# through_hole_mk1.net
KiCad netlist of a schematic drawn in EAGLE
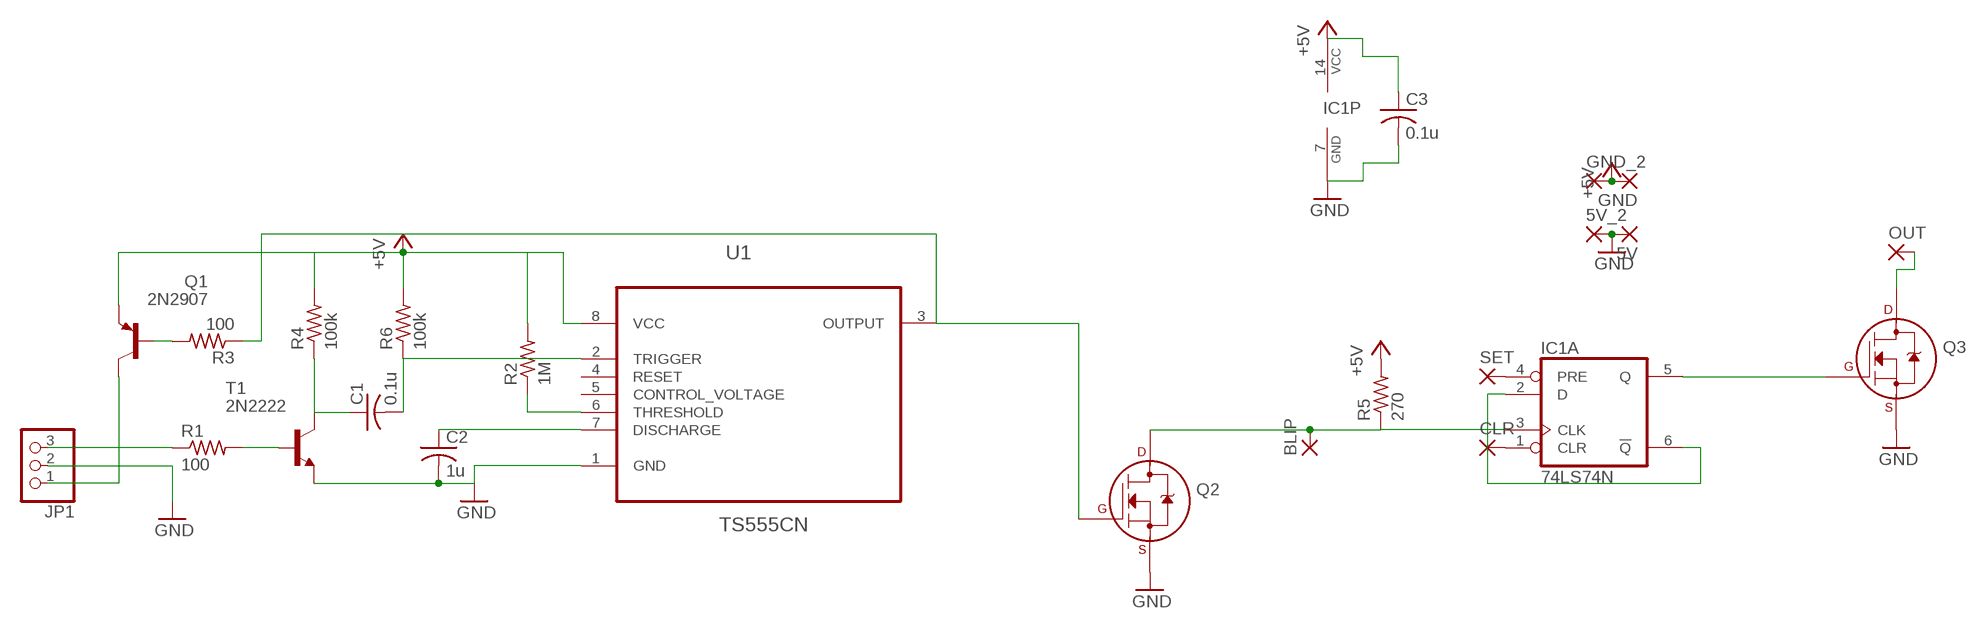
[diagram p0: schematic, sheet 1]

(export (version "E")
  (design (tool "Eeschema 10.0.6"))
  (components
    (comp (ref "5V")
      (value "1,6/0,8")
      (footprint "eagle-import:1,6_0,8")
      (libsource (lib "eagle-import") (part "1,6/0,8"))
    )
    (comp (ref "5V_2")
      (value "1,6/0,8")
      (footprint "eagle-import:1,6_0,8")
      (libsource (lib "eagle-import") (part "1,6/0,8"))
    )
    (comp (ref "BLIP")
      (value "1,6/0,8")
      (footprint "eagle-import:1,6_0,8")
      (libsource (lib "eagle-import") (part "1,6/0,8"))
    )
    (comp (ref "C1")
      (value "0.1u")
      (footprint "eagle-import:C025-030X050")
      (libsource (lib "eagle-import") (part "C-US025-030X050"))
    )
    (comp (ref "C2")
      (value "1u")
      (footprint "eagle-import:C025-030X050")
      (libsource (lib "eagle-import") (part "C-US025-030X050"))
    )
    (comp (ref "C3")
      (value "0.1u")
      (footprint "eagle-import:C025-030X050")
      (libsource (lib "eagle-import") (part "C-US025-030X050"))
    )
    (comp (ref "CLR")
      (value "1,6/0,8")
      (footprint "eagle-import:1,6_0,8")
      (libsource (lib "eagle-import") (part "1,6/0,8"))
    )
    (comp (ref "GND")
      (value "1,6/0,8")
      (footprint "eagle-import:1,6_0,8")
      (libsource (lib "eagle-import") (part "1,6/0,8"))
    )
    (comp (ref "GND_2")
      (value "1,6/0,8")
      (footprint "eagle-import:1,6_0,8")
      (libsource (lib "eagle-import") (part "1,6/0,8"))
    )
    (comp (ref "IC1")
      (value "74LS74N")
      (footprint "eagle-import:DIL14")
      (libsource (lib "eagle-import") (part "7474NLS"))
    )
    (comp (ref "JP1")
      (value "PINHD-1X3")
      (footprint "eagle-import:1X03")
      (libsource (lib "eagle-import") (part "PINHD-1X3"))
    )
    (comp (ref "OUT")
      (value "1,6/0,8")
      (footprint "eagle-import:1,6_0,8")
      (libsource (lib "eagle-import") (part "1,6/0,8"))
    )
    (comp (ref "Q1")
      (value "2N2907")
      (footprint "eagle-import:TO92-EBC-OVAL")
      (libsource (lib "eagle-import") (part "2N2907"))
    )
    (comp (ref "Q2")
      (value "2N7000_TO92")
      (footprint "eagle-import:TO-92")
      (libsource (lib "eagle-import") (part "2N700_TO920"))
    )
    (comp (ref "Q3")
      (value "2N7000_TO92")
      (footprint "eagle-import:TO-92")
      (libsource (lib "eagle-import") (part "2N700_TO920"))
    )
    (comp (ref "R1")
      (value "100")
      (footprint "eagle-import:0204_5")
      (libsource (lib "eagle-import") (part "R-US_0204/5"))
    )
    (comp (ref "R2")
      (value "1M")
      (footprint "eagle-import:0204_5")
      (libsource (lib "eagle-import") (part "R-US_0204/5"))
    )
    (comp (ref "R3")
      (value "100")
      (footprint "eagle-import:0204_5")
      (libsource (lib "eagle-import") (part "R-US_0204/5"))
    )
    (comp (ref "R4")
      (value "100k")
      (footprint "eagle-import:0204_5")
      (libsource (lib "eagle-import") (part "R-US_0204/5"))
    )
    (comp (ref "R5")
      (value "270")
      (footprint "eagle-import:0204_5")
      (libsource (lib "eagle-import") (part "R-US_0204/5"))
    )
    (comp (ref "R6")
      (value "100k")
      (footprint "eagle-import:0204_5")
      (libsource (lib "eagle-import") (part "R-US_0204/5"))
    )
    (comp (ref "SET")
      (value "1,6/0,8")
      (footprint "eagle-import:1,6_0,8")
      (libsource (lib "eagle-import") (part "1,6/0,8"))
    )
    (comp (ref "T1")
      (value "2N2222")
      (footprint "eagle-import:TO92-EBC-OVAL")
      (libsource (lib "eagle-import") (part "2N2222"))
    )
    (comp (ref "U1")
      (value "TS555CN")
      (footprint "eagle-import:DIP254P762X533-8")
      (libsource (lib "eagle-import") (part "TS555CN"))
    )
  )
  (nets
    (net (code "1") (name "+5V") (class "Default")
      (node (ref "C3") (pin "1") (pinfunction "1_1") (pintype "passive"))
      (node (ref "GND") (pin "1") (pinfunction "P_1") (pintype "passive"))
      (node (ref "GND_2") (pin "1") (pinfunction "P_1") (pintype "passive"))
      (node (ref "IC1") (pin "14") (pinfunction "VCC_14") (pintype "power_in"))
      (node (ref "Q1") (pin "E") (pinfunction "E_E") (pintype "passive"))
      (node (ref "R2") (pin "2") (pinfunction "2_2") (pintype "passive"))
      (node (ref "R4") (pin "2") (pinfunction "2_2") (pintype "passive"))
      (node (ref "R5") (pin "2") (pinfunction "2_2") (pintype "passive"))
      (node (ref "R6") (pin "2") (pinfunction "2_2") (pintype "passive"))
      (node (ref "U1") (pin "8") (pinfunction "VCC_8") (pintype "power_in"))
    )
    (net (code "2") (name "GND") (class "Default")
      (node (ref "5V") (pin "1") (pinfunction "P_1") (pintype "passive"))
      (node (ref "5V_2") (pin "1") (pinfunction "P_1") (pintype "passive"))
      (node (ref "C2") (pin "2") (pinfunction "2_2") (pintype "passive"))
      (node (ref "C3") (pin "2") (pinfunction "2_2") (pintype "passive"))
      (node (ref "IC1") (pin "7") (pinfunction "GND_7") (pintype "power_in"))
      (node (ref "JP1") (pin "2") (pinfunction "2_2") (pintype "passive"))
      (node (ref "Q2") (pin "1") (pinfunction "S_1") (pintype "bidirectional"))
      (node (ref "Q3") (pin "1") (pinfunction "S_1") (pintype "bidirectional"))
      (node (ref "T1") (pin "E") (pinfunction "E_E") (pintype "passive"))
      (node (ref "U1") (pin "1") (pinfunction "GND_1") (pintype "passive"))
    )
    (net (code "3") (name "Net-(BLIP-P)") (class "Default")
      (node (ref "BLIP") (pin "1") (pinfunction "P_1") (pintype "passive"))
      (node (ref "IC1") (pin "3") (pinfunction "CLK_3") (pintype "input"))
      (node (ref "Q2") (pin "3") (pinfunction "D_3") (pintype "bidirectional"))
      (node (ref "R5") (pin "1") (pinfunction "1_1") (pintype "passive"))
    )
    (net (code "4") (name "Net-(C1-Pad1)") (class "Default")
      (node (ref "C1") (pin "1") (pinfunction "1_1") (pintype "passive"))
      (node (ref "R4") (pin "1") (pinfunction "1_1") (pintype "passive"))
      (node (ref "T1") (pin "C") (pinfunction "C_C") (pintype "passive"))
    )
    (net (code "5") (name "Net-(CLR-P)") (class "Default")
      (node (ref "CLR") (pin "1") (pinfunction "P_1") (pintype "passive"))
      (node (ref "IC1") (pin "1") (pinfunction "CLR_1") (pintype "input"))
    )
    (net (code "6") (name "Net-(IC1A-D)") (class "Default")
      (node (ref "IC1") (pin "2") (pinfunction "D_2") (pintype "input"))
      (node (ref "IC1") (pin "6") (pinfunction "~{Q}_6") (pintype "output"))
    )
    (net (code "7") (name "Net-(IC1A-PRE)") (class "Default")
      (node (ref "IC1") (pin "4") (pinfunction "PRE_4") (pintype "input"))
      (node (ref "SET") (pin "1") (pinfunction "P_1") (pintype "passive"))
    )
    (net (code "8") (name "Net-(IC1A-Q)") (class "Default")
      (node (ref "IC1") (pin "5") (pinfunction "Q_5") (pintype "output"))
      (node (ref "Q3") (pin "2") (pinfunction "G_2") (pintype "tri_state"))
    )
    (net (code "9") (name "Net-(JP1-Pad1)") (class "Default")
      (node (ref "JP1") (pin "1") (pinfunction "1_1") (pintype "passive"))
      (node (ref "Q1") (pin "C") (pinfunction "C_C") (pintype "passive"))
    )
    (net (code "10") (name "Net-(JP1-Pad3)") (class "Default")
      (node (ref "JP1") (pin "3") (pinfunction "3_3") (pintype "passive"))
      (node (ref "R1") (pin "1") (pinfunction "1_1") (pintype "passive"))
    )
    (net (code "11") (name "Net-(OUT-P)") (class "Default")
      (node (ref "OUT") (pin "1") (pinfunction "P_1") (pintype "passive"))
      (node (ref "Q3") (pin "3") (pinfunction "D_3") (pintype "bidirectional"))
    )
    (net (code "12") (name "Net-(Q1-PadB)") (class "Default")
      (node (ref "Q1") (pin "B") (pinfunction "B_B") (pintype "passive"))
      (node (ref "R3") (pin "2") (pinfunction "2_2") (pintype "passive"))
    )
    (net (code "13") (name "Net-(Q2-G)") (class "Default")
      (node (ref "Q2") (pin "2") (pinfunction "G_2") (pintype "tri_state"))
      (node (ref "R3") (pin "1") (pinfunction "1_1") (pintype "passive"))
      (node (ref "U1") (pin "3") (pinfunction "OUTPUT_3") (pintype "output"))
    )
    (net (code "14") (name "Net-(R1-Pad2)") (class "Default")
      (node (ref "R1") (pin "2") (pinfunction "2_2") (pintype "passive"))
      (node (ref "T1") (pin "B") (pinfunction "B_B") (pintype "passive"))
    )
    (net (code "15") (name "Net-(U1-DISCHARGE)") (class "Default")
      (node (ref "C2") (pin "1") (pinfunction "1_1") (pintype "passive"))
      (node (ref "U1") (pin "7") (pinfunction "DISCHARGE_7") (pintype "passive"))
    )
    (net (code "16") (name "Net-(U1-THRESHOLD)") (class "Default")
      (node (ref "R2") (pin "1") (pinfunction "1_1") (pintype "passive"))
      (node (ref "U1") (pin "6") (pinfunction "THRESHOLD_6") (pintype "input"))
    )
    (net (code "17") (name "Net-(U1-TRIGGER)") (class "Default")
      (node (ref "C1") (pin "2") (pinfunction "2_2") (pintype "passive"))
      (node (ref "R6") (pin "1") (pinfunction "1_1") (pintype "passive"))
      (node (ref "U1") (pin "2") (pinfunction "TRIGGER_2") (pintype "input"))
    )
    (net (code "18") (name "unconnected-(U1-CONTROL_VOLTAGE-Pad5)") (class "Default")
      (node (ref "U1") (pin "5") (pinfunction "CONTROL_VOLTAGE_5") (pintype "input"))
    )
    (net (code "19") (name "unconnected-(U1-RESET-Pad4)") (class "Default")
      (node (ref "U1") (pin "4") (pinfunction "RESET_4") (pintype "input"))
    )
  )
)
